# Commodore_CPM_Modul.net
KiCad netlist of a schematic drawn in Altium Designer
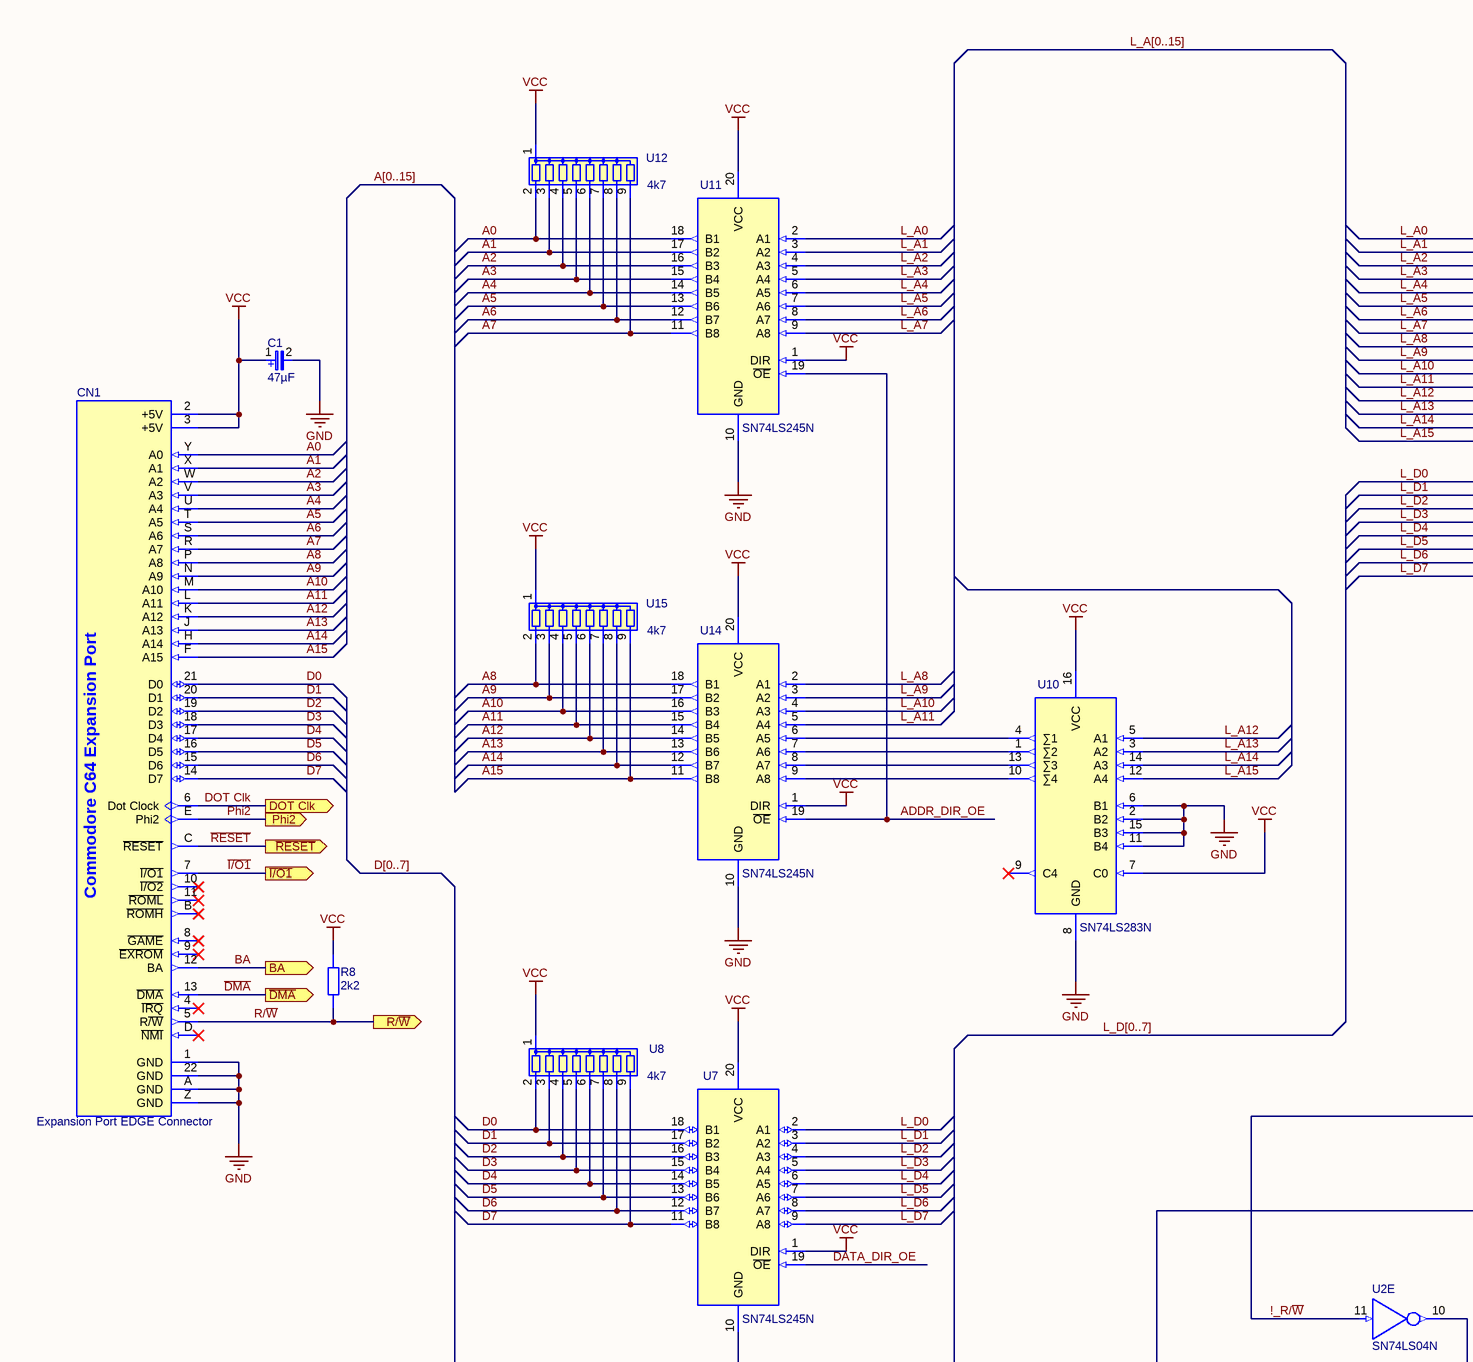
[diagram p0: Commodore CPM Modul.SchDoc, top left]
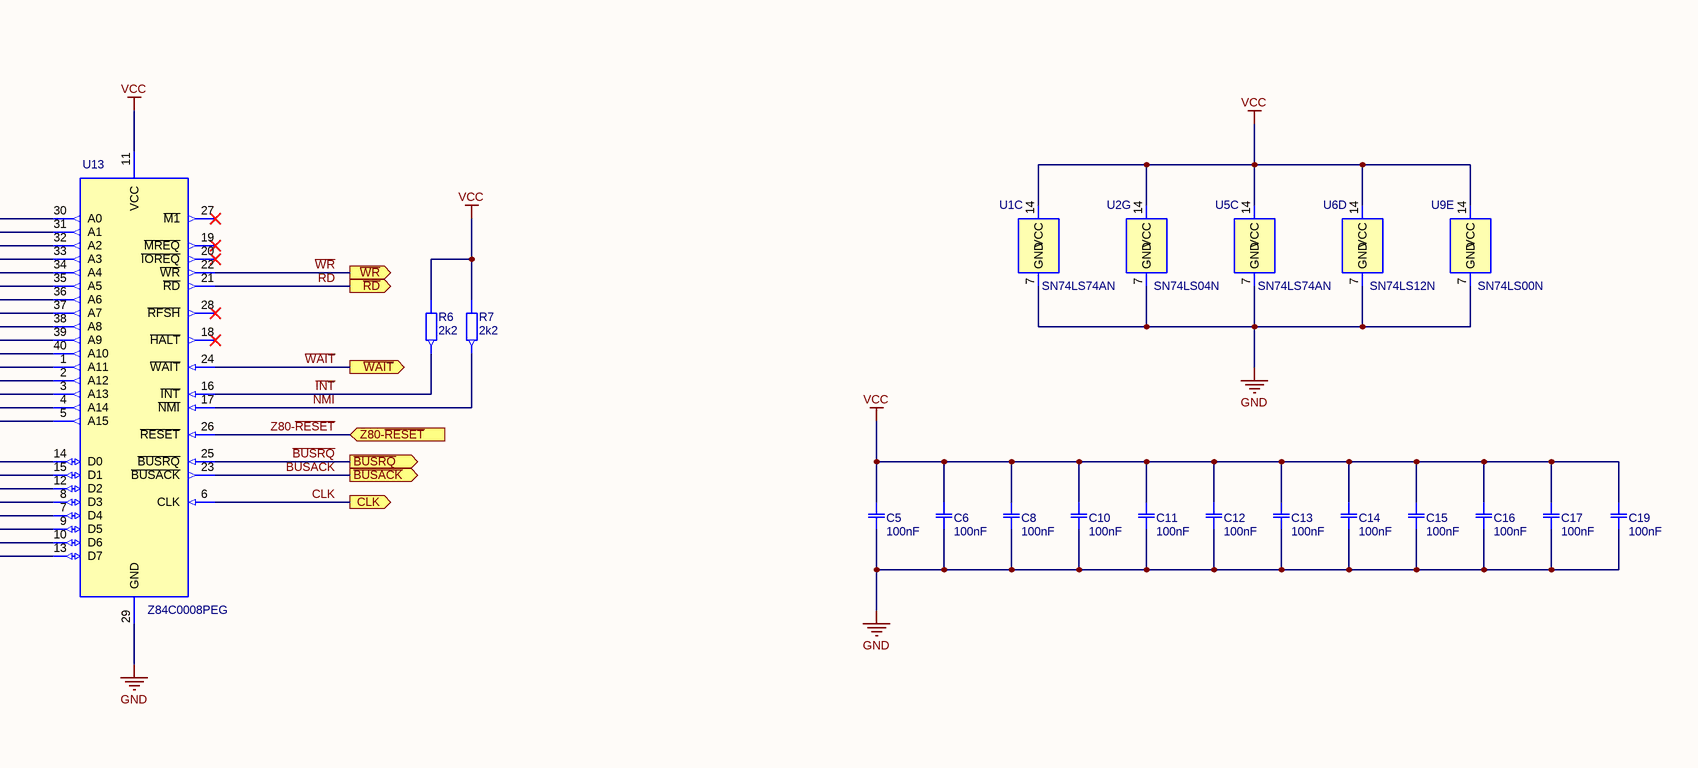
[diagram p1: Commodore CPM Modul.SchDoc, top right]
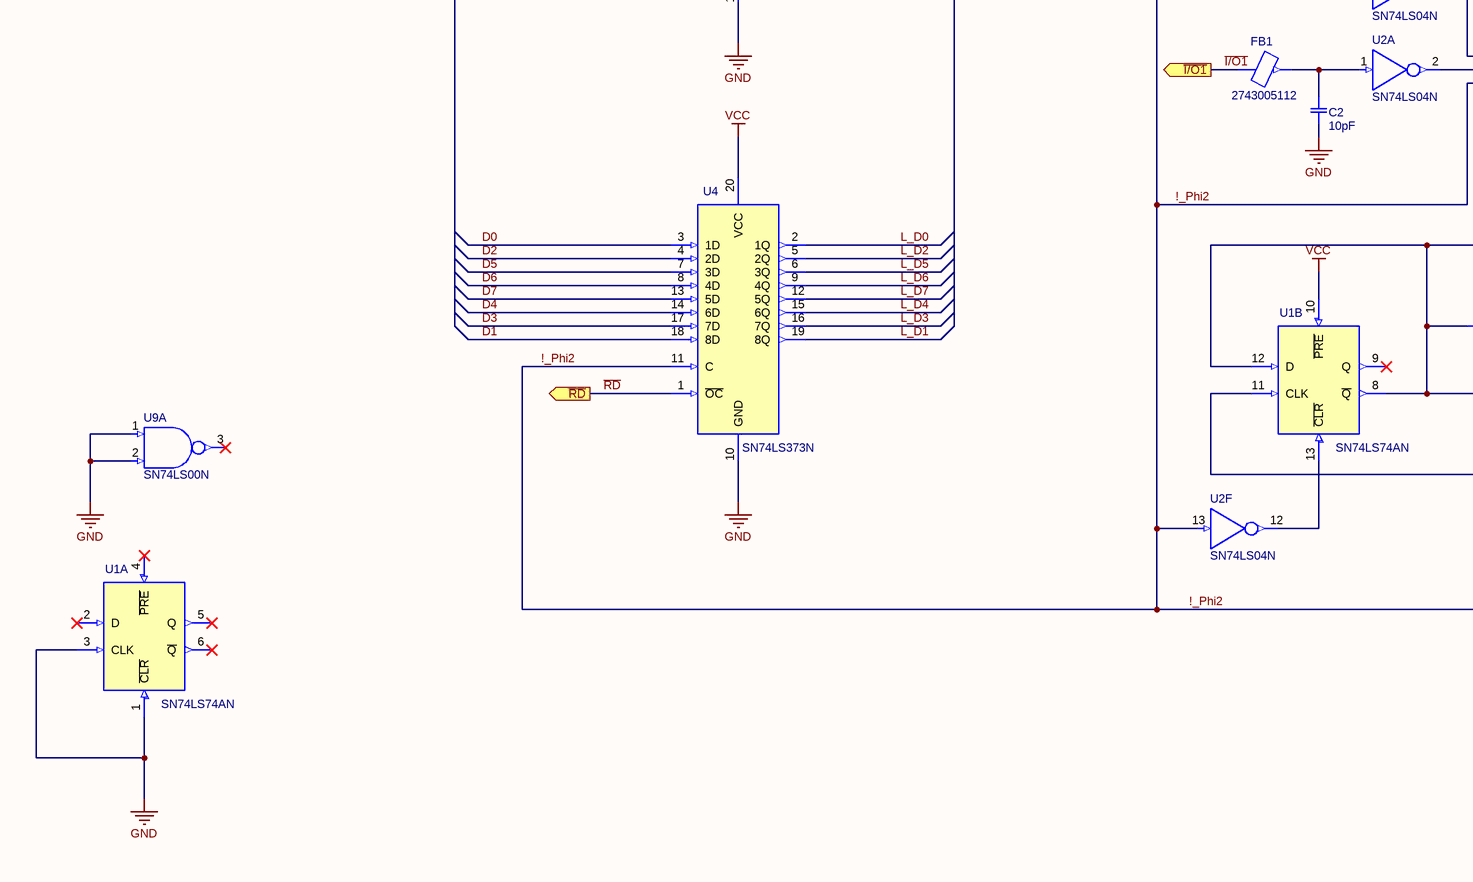
[diagram p2: Commodore CPM Modul.SchDoc, bottom left]
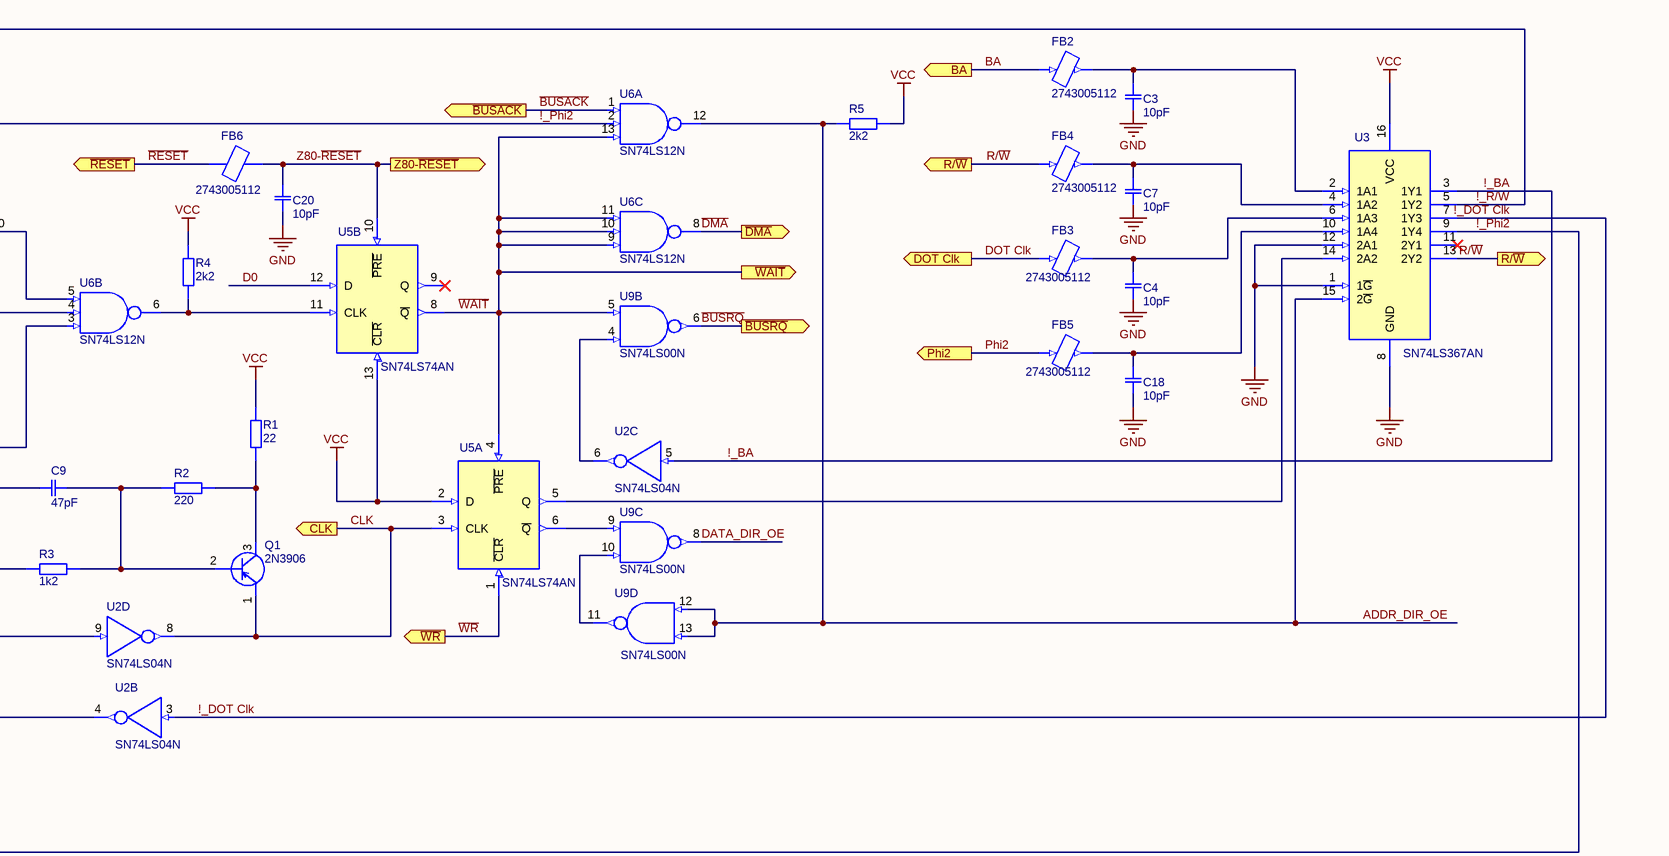
[diagram p3: Commodore CPM Modul.SchDoc, bottom right]

(export (version "E")
  (design (tool "Eeschema 10.0.6"))
  (components
    (comp (ref "C1")
      (value "47µF")
      (footprint "CAP Elec 47uF 25V Axial - Vishay MAL203036479E3")
      (description "Cap Aluminum 47uF 25V -10% to 50% (6 X 10mm) Axial 4.8 Ohm 100mA 3000 hr 85C Taped in Box")
      (fields (field (name "VOLTAGE") "25V") (field (name "TOLERANCE") "50%"))
      (libsource (lib "PCB-Tech Cloud") (part "Polarized Capacitor"))
    )
    (comp (ref "C2")
      (value "10pF")
      (footprint "CAP CER 10PF 50V C0G/NP0 AXIAL Vishay A100J15C0GF5TAA")
      (description "Cap Ceramic 10pF 50V C0G 5% Axial 125C T/R")
      (fields (field (name "TOLERANCE") "5%"))
      (libsource (lib "PCB-Tech Cloud") (part "Capacitor"))
    )
    (comp (ref "C3")
      (value "10pF")
      (footprint "CAP CER 10PF 50V C0G/NP0 AXIAL Vishay A100J15C0GF5TAA")
      (description "Cap Ceramic 10pF 50V C0G 5% Axial 125C T/R")
      (fields (field (name "TOLERANCE") "5%"))
      (libsource (lib "PCB-Tech Cloud") (part "Capacitor"))
    )
    (comp (ref "C4")
      (value "10pF")
      (footprint "CAP CER 10PF 50V C0G/NP0 AXIAL Vishay A100J15C0GF5TAA")
      (description "Cap Ceramic 10pF 50V C0G 5% Axial 125C T/R")
      (fields (field (name "TOLERANCE") "5%"))
      (libsource (lib "PCB-Tech Cloud") (part "Capacitor"))
    )
    (comp (ref "C5")
      (value "100nF")
      (footprint "CAP CER 0.1UF 50V X7R RADIAL Kemet C330C104J5R5TA")
      (description "Cap Ceramic 0.1uF 50V X7R 5% Radial 5.08mm 125C Bulk")
      (fields (field (name "TOLERANCE") "5%"))
      (libsource (lib "PCB-Tech Cloud") (part "Capacitor"))
    )
    (comp (ref "C6")
      (value "100nF")
      (footprint "CAP CER 0.1UF 50V X7R RADIAL Kemet C330C104J5R5TA")
      (description "Cap Ceramic 0.1uF 50V X7R 5% Radial 5.08mm 125C Bulk")
      (fields (field (name "TOLERANCE") "5%"))
      (libsource (lib "PCB-Tech Cloud") (part "Capacitor"))
    )
    (comp (ref "C7")
      (value "10pF")
      (footprint "CAP CER 10PF 50V C0G/NP0 AXIAL Vishay A100J15C0GF5TAA")
      (description "Cap Ceramic 10pF 50V C0G 5% Axial 125C T/R")
      (fields (field (name "TOLERANCE") "5%"))
      (libsource (lib "PCB-Tech Cloud") (part "Capacitor"))
    )
    (comp (ref "C8")
      (value "100nF")
      (footprint "CAP CER 0.1UF 50V X7R RADIAL Kemet C330C104J5R5TA")
      (description "Cap Ceramic 0.1uF 50V X7R 5% Radial 5.08mm 125C Bulk")
      (fields (field (name "TOLERANCE") "5%"))
      (libsource (lib "PCB-Tech Cloud") (part "Capacitor"))
    )
    (comp (ref "C9")
      (value "47pF")
      (footprint "CAP CER 47PF 50V C0G/NP0 AXIAL Vishay A470J15C0GF5TAA")
      (description "Cap Ceramic 47pF 50V C0G 5% Axial 125C T/R")
      (fields (field (name "TOLERANCE") "5%"))
      (libsource (lib "PCB-Tech Cloud") (part "Capacitor"))
    )
    (comp (ref "C10")
      (value "100nF")
      (footprint "CAP CER 0.1UF 50V X7R RADIAL Kemet C330C104J5R5TA")
      (description "Cap Ceramic 0.1uF 50V X7R 5% Radial 5.08mm 125C Bulk")
      (fields (field (name "TOLERANCE") "5%"))
      (libsource (lib "PCB-Tech Cloud") (part "Capacitor"))
    )
    (comp (ref "C11")
      (value "100nF")
      (footprint "CAP CER 0.1UF 50V X7R RADIAL Kemet C330C104J5R5TA")
      (description "Cap Ceramic 0.1uF 50V X7R 5% Radial 5.08mm 125C Bulk")
      (fields (field (name "TOLERANCE") "5%"))
      (libsource (lib "PCB-Tech Cloud") (part "Capacitor"))
    )
    (comp (ref "C12")
      (value "100nF")
      (footprint "CAP CER 0.1UF 50V X7R RADIAL Kemet C330C104J5R5TA")
      (description "Cap Ceramic 0.1uF 50V X7R 5% Radial 5.08mm 125C Bulk")
      (fields (field (name "TOLERANCE") "5%"))
      (libsource (lib "PCB-Tech Cloud") (part "Capacitor"))
    )
    (comp (ref "C13")
      (value "100nF")
      (footprint "CAP CER 0.1UF 50V X7R RADIAL Kemet C330C104J5R5TA")
      (description "Cap Ceramic 0.1uF 50V X7R 5% Radial 5.08mm 125C Bulk")
      (fields (field (name "TOLERANCE") "5%"))
      (libsource (lib "PCB-Tech Cloud") (part "Capacitor"))
    )
    (comp (ref "C14")
      (value "100nF")
      (footprint "CAP CER 0.1UF 50V X7R RADIAL Kemet C330C104J5R5TA")
      (description "Cap Ceramic 0.1uF 50V X7R 5% Radial 5.08mm 125C Bulk")
      (fields (field (name "TOLERANCE") "5%"))
      (libsource (lib "PCB-Tech Cloud") (part "Capacitor"))
    )
    (comp (ref "C15")
      (value "100nF")
      (footprint "CAP CER 0.1UF 50V X7R RADIAL Kemet C330C104J5R5TA")
      (description "Cap Ceramic 0.1uF 50V X7R 5% Radial 5.08mm 125C Bulk")
      (fields (field (name "TOLERANCE") "5%"))
      (libsource (lib "PCB-Tech Cloud") (part "Capacitor"))
    )
    (comp (ref "C16")
      (value "100nF")
      (footprint "CAP CER 0.1UF 50V X7R RADIAL Kemet C330C104J5R5TA")
      (description "Cap Ceramic 0.1uF 50V X7R 5% Radial 5.08mm 125C Bulk")
      (fields (field (name "TOLERANCE") "5%"))
      (libsource (lib "PCB-Tech Cloud") (part "Capacitor"))
    )
    (comp (ref "C17")
      (value "100nF")
      (footprint "CAP CER 0.1UF 50V X7R RADIAL Kemet C330C104J5R5TA")
      (description "Cap Ceramic 0.1uF 50V X7R 5% Radial 5.08mm 125C Bulk")
      (fields (field (name "TOLERANCE") "5%"))
      (libsource (lib "PCB-Tech Cloud") (part "Capacitor"))
    )
    (comp (ref "C18")
      (value "10pF")
      (footprint "CAP CER 10PF 50V C0G/NP0 AXIAL Vishay A100J15C0GF5TAA")
      (description "Cap Ceramic 10pF 50V C0G 5% Axial 125C T/R")
      (fields (field (name "TOLERANCE") "5%"))
      (libsource (lib "PCB-Tech Cloud") (part "Capacitor"))
    )
    (comp (ref "C19")
      (value "100nF")
      (footprint "CAP CER 0.1UF 50V X7R RADIAL Kemet C330C104J5R5TA")
      (description "Cap Ceramic 0.1uF 50V X7R 5% Radial 5.08mm 125C Bulk")
      (fields (field (name "TOLERANCE") "5%"))
      (libsource (lib "PCB-Tech Cloud") (part "Capacitor"))
    )
    (comp (ref "C20")
      (value "10pF")
      (footprint "CAP CER 10PF 50V C0G/NP0 AXIAL Vishay A100J15C0GF5TAA")
      (description "Cap Ceramic 10pF 50V C0G 5% Axial 125C T/R")
      (fields (field (name "TOLERANCE") "5%"))
      (libsource (lib "PCB-Tech Cloud") (part "Capacitor"))
    )
    (comp (ref "CN1")
      (value "Expansion Port EDGE Connector")
      (footprint "C64 Expansion Port EDGE Connector")
      (description "Expansion Port EDGE Connector for Interface Cards")
      (libsource (lib "PCB-Tech Cloud") (part "C64 Expansion Port"))
    )
    (comp (ref "FB1")
      (value "2743005112")
      (footprint "Ferrite Bead Fair Rite 2743005112 axial 10,16mm")
      (description "Ferrite Beads Axial 91Ohm 100MHz T/R")
      (libsource (lib "PCB-Tech Cloud") (part "Ferrite Bead"))
    )
    (comp (ref "FB2")
      (value "2743005112")
      (footprint "Ferrite Bead Fair Rite 2743005112 axial 10,16mm")
      (description "Ferrite Beads Axial 91Ohm 100MHz T/R")
      (libsource (lib "PCB-Tech Cloud") (part "Ferrite Bead"))
    )
    (comp (ref "FB3")
      (value "2743005112")
      (footprint "Ferrite Bead Fair Rite 2743005112 axial 10,16mm")
      (description "Ferrite Beads Axial 91Ohm 100MHz T/R")
      (libsource (lib "PCB-Tech Cloud") (part "Ferrite Bead"))
    )
    (comp (ref "FB4")
      (value "2743005112")
      (footprint "Ferrite Bead Fair Rite 2743005112 axial 10,16mm")
      (description "Ferrite Beads Axial 91Ohm 100MHz T/R")
      (libsource (lib "PCB-Tech Cloud") (part "Ferrite Bead"))
    )
    (comp (ref "FB5")
      (value "2743005112")
      (footprint "Ferrite Bead Fair Rite 2743005112 axial 10,16mm")
      (description "Ferrite Beads Axial 91Ohm 100MHz T/R")
      (libsource (lib "PCB-Tech Cloud") (part "Ferrite Bead"))
    )
    (comp (ref "FB6")
      (value "2743005112")
      (footprint "Ferrite Bead Fair Rite 2743005112 axial 10,16mm")
      (description "Ferrite Beads Axial 91Ohm 100MHz T/R")
      (libsource (lib "PCB-Tech Cloud") (part "Ferrite Bead"))
    )
    (comp (ref "Q1")
      (value "2N3906")
      (footprint "2N3906")
      (description "Bipolar Transistor PNP Amplifier/Switch 40V 200mA 3-Pin TO-92 Through Hole Box")
      (libsource (lib "PCB-Tech Cloud") (part "Transistor PNP EBC"))
    )
    (comp (ref "R1")
      (value "22")
      (footprint "22 Ohm R Axial DIN0207 L6.3mm D2.5mm P10.16mm Horizontal")
      (description "RES 22 OHM 1/4W 5% AXIAL")
      (fields (field (name "TOLERANCE") "5%"))
      (libsource (lib "PCB-Tech Cloud") (part "Resistor"))
    )
    (comp (ref "R2")
      (value "220")
      (footprint "220 Ohm R Axial DIN0207 L6.3mm D2.5mm P10.16mm Horizontal")
      (description "RES 220 OHM 1/4W 5% AXIAL")
      (fields (field (name "TOLERANCE") "5%"))
      (libsource (lib "PCB-Tech Cloud") (part "Resistor"))
    )
    (comp (ref "R3")
      (value "1k2")
      (footprint "1,2 kOhm R Axial DIN0207 L6.3mm D2.5mm P10.16mm Horizontal")
      (description "RES 1.2K OHM 1/4W 5% AXIAL")
      (fields (field (name "TOLERANCE") "5%"))
      (libsource (lib "PCB-Tech Cloud") (part "Resistor"))
    )
    (comp (ref "R4")
      (value "2k2")
      (footprint "2,2 kOhm R Axial DIN0207 L6.3mm D2.5mm P10.16mm Horizontal")
      (description "RES 2.2K OHM 1/4W 5% AXIAL")
      (fields (field (name "TOLERANCE") "5%"))
      (libsource (lib "PCB-Tech Cloud") (part "Resistor"))
    )
    (comp (ref "R5")
      (value "2k2")
      (footprint "2,2 kOhm R Axial DIN0207 L6.3mm D2.5mm P10.16mm Horizontal")
      (description "RES 2.2K OHM 1/4W 5% AXIAL")
      (fields (field (name "TOLERANCE") "5%"))
      (libsource (lib "PCB-Tech Cloud") (part "Resistor"))
    )
    (comp (ref "R6")
      (value "2k2")
      (footprint "2,2 kOhm R Axial DIN0207 L6.3mm D2.5mm P10.16mm Horizontal")
      (description "RES 2.2K OHM 1/4W 5% AXIAL")
      (fields (field (name "TOLERANCE") "5%"))
      (libsource (lib "") (part "Resistor_1"))
    )
    (comp (ref "R7")
      (value "2k2")
      (footprint "2,2 kOhm R Axial DIN0207 L6.3mm D2.5mm P10.16mm Horizontal")
      (description "RES 2.2K OHM 1/4W 5% AXIAL")
      (fields (field (name "TOLERANCE") "5%"))
      (libsource (lib "") (part "Resistor_1"))
    )
    (comp (ref "R8")
      (value "2k2")
      (footprint "2,2 kOhm R Axial DIN0207 L6.3mm D2.5mm P10.16mm Horizontal")
      (description "RES 2.2K OHM 1/4W 5% AXIAL")
      (fields (field (name "TOLERANCE") "5%"))
      (libsource (lib "PCB-Tech Cloud") (part "Resistor"))
    )
    (comp (ref "U1")
      (value "SN74LS74AN")
      (footprint "SN74LS74N with Socket")
      (libsource (lib "PCB-Tech Cloud") (part "74xx74"))
    )
    (comp (ref "U2")
      (value "SN74LS04N")
      (footprint "SN74LS04N with Socket")
      (description "IC HEX INVERTER 14-DIP")
      (libsource (lib "PCB-Tech Cloud") (part "74xx04"))
    )
    (comp (ref "U3")
      (value "SN74LS367AN")
      (footprint "SN74LS367A with Socket")
      (description "I.C. SN74LS 367 AN")
      (libsource (lib "PCB-Tech Cloud") (part "74xx367"))
    )
    (comp (ref "U4")
      (value "SN74LS373N")
      (footprint "SN74LS373N with Socket")
      (description "Latch Transparent 3-ST 8-CH D-Type 20-Pin PDIP Tube")
      (libsource (lib "PCB-Tech Cloud") (part "74xx373"))
    )
    (comp (ref "U5")
      (value "SN74LS74AN")
      (footprint "SN74LS74N with Socket")
      (libsource (lib "PCB-Tech Cloud") (part "74xx74"))
    )
    (comp (ref "U6")
      (value "SN74LS12N")
      (footprint "SN74LS12N with Socket")
      (description "Logic Gates Triple 3-input Positive-NAND gates with open collector outputs 14-PDIP 0 to 70")
      (libsource (lib "") (part "74xx12_1"))
    )
    (comp (ref "U7")
      (value "SN74LS245N")
      (footprint "SN74LS245N with Socket")
      (description "IC TXRX NON-INVERT 5.25V 20DIP")
      (libsource (lib "PCB-Tech Cloud") (part "74xx245"))
    )
    (comp (ref "U8")
      (value "4k7")
      (footprint "4k7 x8 Resistor Array SIL Royal 9A472G")
      (description "Resistor Networks & Arrays 9pin 4.7Kohms 2% Bussed")
      (fields (field (name "TOLERANCE") "2%"))
      (libsource (lib "PCB-Tech Cloud") (part "Resistor Network x8"))
    )
    (comp (ref "U9")
      (value "SN74LS00N")
      (footprint "SN74LS00N with Socket")
      (description "IC, 74LS, 74LS00, DIP14, 5.25V")
      (libsource (lib "") (part "74xx00_2"))
    )
    (comp (ref "U10")
      (value "SN74LS283N")
      (footprint "SN74LS283N with Socket")
      (description "Binary Full Adder Single 4-Bit 16-Pin PDIP Box")
      (libsource (lib "PCB-Tech Cloud") (part "74xx283"))
    )
    (comp (ref "U11")
      (value "SN74LS245N")
      (footprint "SN74LS245N with Socket")
      (description "IC TXRX NON-INVERT 5.25V 20DIP")
      (libsource (lib "PCB-Tech Cloud") (part "74xx245"))
    )
    (comp (ref "U12")
      (value "4k7")
      (footprint "4k7 x8 Resistor Array SIL Royal 9A472G")
      (description "Resistor Networks & Arrays 9pin 4.7Kohms 2% Bussed")
      (fields (field (name "TOLERANCE") "2%"))
      (libsource (lib "PCB-Tech Cloud") (part "Resistor Network x8"))
    )
    (comp (ref "U13")
      (value "Z84C0008PEG")
      (footprint "Zilog Z80 CPU with Socket")
      (description "IC MPU Z80 8MHZ 40DIP")
      (fields (field (name "VOLTAGE") "5V"))
      (libsource (lib "PCB-Tech Cloud") (part "Zilog Z80 CPU"))
    )
    (comp (ref "U14")
      (value "SN74LS245N")
      (footprint "SN74LS245N with Socket")
      (description "IC TXRX NON-INVERT 5.25V 20DIP")
      (libsource (lib "PCB-Tech Cloud") (part "74xx245"))
    )
    (comp (ref "U15")
      (value "4k7")
      (footprint "4k7 x8 Resistor Array SIL Royal 9A472G")
      (description "Resistor Networks & Arrays 9pin 4.7Kohms 2% Bussed")
      (fields (field (name "TOLERANCE") "2%"))
      (libsource (lib "PCB-Tech Cloud") (part "Resistor Network x8"))
    )
  )
  (nets
    (net (code "1") (name "/!_BA") (class "Default")
      (node (ref "U2") (pin "5") (pinfunction "3A_5") (pintype "input"))
      (node (ref "U3") (pin "3") (pinfunction "1Y1_3") (pintype "open_collector"))
    )
    (net (code "2") (name "/!_DOT Clk") (class "Default")
      (node (ref "U2") (pin "3") (pinfunction "2A_3") (pintype "input"))
      (node (ref "U3") (pin "7") (pinfunction "1Y3_7") (pintype "open_collector"))
    )
    (net (code "3") (name "/!_Phi2") (class "Default")
      (node (ref "U2") (pin "13") (pinfunction "6A_13") (pintype "input"))
      (node (ref "U3") (pin "9") (pinfunction "1Y4_9") (pintype "open_collector"))
      (node (ref "U4") (pin "11") (pinfunction "C_11") (pintype "input"))
      (node (ref "U6") (pin "2") (pinfunction "1B_2") (pintype "input"))
      (node (ref "U6") (pin "3") (pinfunction "2A_3") (pintype "input"))
    )
    (net (code "4") (name "/!_R{slash}~{W}") (class "Default")
      (node (ref "U2") (pin "11") (pinfunction "5A_11") (pintype "input"))
      (node (ref "U3") (pin "5") (pinfunction "1Y2_5") (pintype "open_collector"))
    )
    (net (code "5") (name "/A0") (class "Default")
      (node (ref "CN1") (pin "Y") (pinfunction "A0_Y") (pintype "input"))
      (node (ref "U11") (pin "18") (pinfunction "B1_18") (pintype "output"))
      (node (ref "U12") (pin "2") (pinfunction "2_2") (pintype "passive"))
    )
    (net (code "6") (name "/A1") (class "Default")
      (node (ref "CN1") (pin "X") (pinfunction "A1_X") (pintype "input"))
      (node (ref "U11") (pin "17") (pinfunction "B2_17") (pintype "output"))
      (node (ref "U12") (pin "3") (pinfunction "3_3") (pintype "passive"))
    )
    (net (code "7") (name "/A2") (class "Default")
      (node (ref "CN1") (pin "W") (pinfunction "A2_W") (pintype "input"))
      (node (ref "U11") (pin "16") (pinfunction "B3_16") (pintype "output"))
      (node (ref "U12") (pin "4") (pinfunction "4_4") (pintype "passive"))
    )
    (net (code "8") (name "/A3") (class "Default")
      (node (ref "CN1") (pin "V") (pinfunction "A3_V") (pintype "input"))
      (node (ref "U11") (pin "15") (pinfunction "B4_15") (pintype "output"))
      (node (ref "U12") (pin "5") (pinfunction "5_5") (pintype "passive"))
    )
    (net (code "9") (name "/A4") (class "Default")
      (node (ref "CN1") (pin "U") (pinfunction "A4_U") (pintype "input"))
      (node (ref "U11") (pin "14") (pinfunction "B5_14") (pintype "output"))
      (node (ref "U12") (pin "6") (pinfunction "6_6") (pintype "passive"))
    )
    (net (code "10") (name "/A5") (class "Default")
      (node (ref "CN1") (pin "T") (pinfunction "A5_T") (pintype "input"))
      (node (ref "U11") (pin "13") (pinfunction "B6_13") (pintype "output"))
      (node (ref "U12") (pin "7") (pinfunction "7_7") (pintype "passive"))
    )
    (net (code "11") (name "/A6") (class "Default")
      (node (ref "CN1") (pin "S") (pinfunction "A6_S") (pintype "input"))
      (node (ref "U11") (pin "12") (pinfunction "B7_12") (pintype "output"))
      (node (ref "U12") (pin "8") (pinfunction "8_8") (pintype "passive"))
    )
    (net (code "12") (name "/A7") (class "Default")
      (node (ref "CN1") (pin "R") (pinfunction "A7_R") (pintype "input"))
      (node (ref "U11") (pin "11") (pinfunction "B8_11") (pintype "output"))
      (node (ref "U12") (pin "9") (pinfunction "9_9") (pintype "passive"))
    )
    (net (code "13") (name "/A8") (class "Default")
      (node (ref "CN1") (pin "P") (pinfunction "A8_P") (pintype "input"))
      (node (ref "U14") (pin "18") (pinfunction "B1_18") (pintype "output"))
      (node (ref "U15") (pin "2") (pinfunction "2_2") (pintype "passive"))
    )
    (net (code "14") (name "/A9") (class "Default")
      (node (ref "CN1") (pin "N") (pinfunction "A9_N") (pintype "input"))
      (node (ref "U14") (pin "17") (pinfunction "B2_17") (pintype "output"))
      (node (ref "U15") (pin "3") (pinfunction "3_3") (pintype "passive"))
    )
    (net (code "15") (name "/A10") (class "Default")
      (node (ref "CN1") (pin "M") (pinfunction "A10_M") (pintype "input"))
      (node (ref "U14") (pin "16") (pinfunction "B3_16") (pintype "output"))
      (node (ref "U15") (pin "4") (pinfunction "4_4") (pintype "passive"))
    )
    (net (code "16") (name "/A11") (class "Default")
      (node (ref "CN1") (pin "L") (pinfunction "A11_L") (pintype "input"))
      (node (ref "U14") (pin "15") (pinfunction "B4_15") (pintype "output"))
      (node (ref "U15") (pin "5") (pinfunction "5_5") (pintype "passive"))
    )
    (net (code "17") (name "/A12") (class "Default")
      (node (ref "CN1") (pin "K") (pinfunction "A12_K") (pintype "input"))
      (node (ref "U14") (pin "14") (pinfunction "B5_14") (pintype "output"))
      (node (ref "U15") (pin "6") (pinfunction "6_6") (pintype "passive"))
    )
    (net (code "18") (name "/A13") (class "Default")
      (node (ref "CN1") (pin "J") (pinfunction "A13_J") (pintype "input"))
      (node (ref "U14") (pin "13") (pinfunction "B6_13") (pintype "output"))
      (node (ref "U15") (pin "7") (pinfunction "7_7") (pintype "passive"))
    )
    (net (code "19") (name "/A14") (class "Default")
      (node (ref "CN1") (pin "H") (pinfunction "A14_H") (pintype "input"))
      (node (ref "U14") (pin "12") (pinfunction "B7_12") (pintype "output"))
      (node (ref "U15") (pin "8") (pinfunction "8_8") (pintype "passive"))
    )
    (net (code "20") (name "/A15") (class "Default")
      (node (ref "CN1") (pin "F") (pinfunction "A15_F") (pintype "input"))
      (node (ref "U14") (pin "11") (pinfunction "B8_11") (pintype "output"))
      (node (ref "U15") (pin "9") (pinfunction "9_9") (pintype "passive"))
    )
    (net (code "21") (name "/ADDR_DIR_OE") (class "Default")
      (node (ref "R5") (pin "1") (pinfunction "1_1") (pintype "passive"))
      (node (ref "U11") (pin "19") (pinfunction "~{OE}_19") (pintype "input"))
      (node (ref "U14") (pin "19") (pinfunction "~{OE}_19") (pintype "input"))
      (node (ref "U3") (pin "15") (pinfunction "2~{G}_15") (pintype "input"))
      (node (ref "U6") (pin "12") (pinfunction "1Y_12") (pintype "open_collector"))
      (node (ref "U9") (pin "12") (pinfunction "4B_12") (pintype "input"))
      (node (ref "U9") (pin "13") (pinfunction "4A_13") (pintype "input"))
    )
    (net (code "23") (name "/BA") (class "Default")
      (node (ref "CN1") (pin "12") (pinfunction "BA_12") (pintype "output"))
      (node (ref "FB2") (pin "1") (pinfunction "1_1") (pintype "passive"))
    )
    (net (code "24") (name "/CLK") (class "Default")
      (node (ref "Q1") (pin "1") (pinfunction "1_1") (pintype "passive"))
      (node (ref "U13") (pin "6") (pinfunction "CLK_6") (pintype "input"))
      (node (ref "U2") (pin "8") (pinfunction "4Y_8") (pintype "output"))
      (node (ref "U5") (pin "3") (pinfunction "CLK_3") (pintype "input"))
    )
    (net (code "25") (name "/D0") (class "Default")
      (node (ref "CN1") (pin "21") (pinfunction "D0_21") (pintype "bidirectional"))
      (node (ref "U4") (pin "3") (pinfunction "1D_3") (pintype "input"))
      (node (ref "U5") (pin "12") (pinfunction "D_12") (pintype "input"))
      (node (ref "U7") (pin "18") (pinfunction "B1_18") (pintype "output"))
      (node (ref "U8") (pin "2") (pinfunction "2_2") (pintype "passive"))
    )
    (net (code "26") (name "/D1") (class "Default")
      (node (ref "CN1") (pin "20") (pinfunction "D1_20") (pintype "bidirectional"))
      (node (ref "U4") (pin "18") (pinfunction "8D_18") (pintype "input"))
      (node (ref "U7") (pin "17") (pinfunction "B2_17") (pintype "output"))
      (node (ref "U8") (pin "3") (pinfunction "3_3") (pintype "passive"))
    )
    (net (code "27") (name "/D2") (class "Default")
      (node (ref "CN1") (pin "19") (pinfunction "D2_19") (pintype "bidirectional"))
      (node (ref "U4") (pin "4") (pinfunction "2D_4") (pintype "input"))
      (node (ref "U7") (pin "16") (pinfunction "B3_16") (pintype "output"))
      (node (ref "U8") (pin "4") (pinfunction "4_4") (pintype "passive"))
    )
    (net (code "28") (name "/D3") (class "Default")
      (node (ref "CN1") (pin "18") (pinfunction "D3_18") (pintype "bidirectional"))
      (node (ref "U4") (pin "17") (pinfunction "7D_17") (pintype "input"))
      (node (ref "U7") (pin "15") (pinfunction "B4_15") (pintype "output"))
      (node (ref "U8") (pin "5") (pinfunction "5_5") (pintype "passive"))
    )
    (net (code "29") (name "/D4") (class "Default")
      (node (ref "CN1") (pin "17") (pinfunction "D4_17") (pintype "bidirectional"))
      (node (ref "U4") (pin "14") (pinfunction "6D_14") (pintype "input"))
      (node (ref "U7") (pin "14") (pinfunction "B5_14") (pintype "output"))
      (node (ref "U8") (pin "6") (pinfunction "6_6") (pintype "passive"))
    )
    (net (code "30") (name "/D5") (class "Default")
      (node (ref "CN1") (pin "16") (pinfunction "D5_16") (pintype "bidirectional"))
      (node (ref "U4") (pin "7") (pinfunction "3D_7") (pintype "input"))
      (node (ref "U7") (pin "13") (pinfunction "B6_13") (pintype "output"))
      (node (ref "U8") (pin "7") (pinfunction "7_7") (pintype "passive"))
    )
    (net (code "31") (name "/D6") (class "Default")
      (node (ref "CN1") (pin "15") (pinfunction "D6_15") (pintype "bidirectional"))
      (node (ref "U4") (pin "8") (pinfunction "4D_8") (pintype "input"))
      (node (ref "U7") (pin "12") (pinfunction "B7_12") (pintype "output"))
      (node (ref "U8") (pin "8") (pinfunction "8_8") (pintype "passive"))
    )
    (net (code "32") (name "/D7") (class "Default")
      (node (ref "CN1") (pin "14") (pinfunction "D7_14") (pintype "bidirectional"))
      (node (ref "U4") (pin "13") (pinfunction "5D_13") (pintype "input"))
      (node (ref "U7") (pin "11") (pinfunction "B8_11") (pintype "output"))
      (node (ref "U8") (pin "9") (pinfunction "9_9") (pintype "passive"))
    )
    (net (code "33") (name "/DATA_DIR_OE") (class "Default")
      (node (ref "U7") (pin "19") (pinfunction "~{OE}_19") (pintype "input"))
      (node (ref "U9") (pin "8") (pinfunction "3Y_8") (pintype "output"))
    )
    (net (code "34") (name "/DOT Clk") (class "Default")
      (node (ref "CN1") (pin "6") (pinfunction "Dot_Clock_6") (pintype "output"))
      (node (ref "FB3") (pin "1") (pinfunction "1_1") (pintype "passive"))
    )
    (net (code "36") (name "/L_A0") (class "Default")
      (node (ref "U11") (pin "2") (pinfunction "A1_2") (pintype "input"))
      (node (ref "U13") (pin "30") (pinfunction "A0_30") (pintype "output"))
    )
    (net (code "37") (name "/L_A1") (class "Default")
      (node (ref "U11") (pin "3") (pinfunction "A2_3") (pintype "input"))
      (node (ref "U13") (pin "31") (pinfunction "A1_31") (pintype "output"))
    )
    (net (code "38") (name "/L_A2") (class "Default")
      (node (ref "U11") (pin "4") (pinfunction "A3_4") (pintype "input"))
      (node (ref "U13") (pin "32") (pinfunction "A2_32") (pintype "output"))
    )
    (net (code "39") (name "/L_A3") (class "Default")
      (node (ref "U11") (pin "5") (pinfunction "A4_5") (pintype "input"))
      (node (ref "U13") (pin "33") (pinfunction "A3_33") (pintype "output"))
    )
    (net (code "40") (name "/L_A4") (class "Default")
      (node (ref "U11") (pin "6") (pinfunction "A5_6") (pintype "input"))
      (node (ref "U13") (pin "34") (pinfunction "A4_34") (pintype "output"))
    )
    (net (code "41") (name "/L_A5") (class "Default")
      (node (ref "U11") (pin "7") (pinfunction "A6_7") (pintype "input"))
      (node (ref "U13") (pin "35") (pinfunction "A5_35") (pintype "output"))
    )
    (net (code "42") (name "/L_A6") (class "Default")
      (node (ref "U11") (pin "8") (pinfunction "A7_8") (pintype "input"))
      (node (ref "U13") (pin "36") (pinfunction "A6_36") (pintype "output"))
    )
    (net (code "43") (name "/L_A7") (class "Default")
      (node (ref "U11") (pin "9") (pinfunction "A8_9") (pintype "input"))
      (node (ref "U13") (pin "37") (pinfunction "A7_37") (pintype "output"))
    )
    (net (code "44") (name "/L_A8") (class "Default")
      (node (ref "U13") (pin "38") (pinfunction "A8_38") (pintype "output"))
      (node (ref "U14") (pin "2") (pinfunction "A1_2") (pintype "input"))
    )
    (net (code "45") (name "/L_A9") (class "Default")
      (node (ref "U13") (pin "39") (pinfunction "A9_39") (pintype "output"))
      (node (ref "U14") (pin "3") (pinfunction "A2_3") (pintype "input"))
    )
    (net (code "46") (name "/L_A10") (class "Default")
      (node (ref "U13") (pin "40") (pinfunction "A10_40") (pintype "output"))
      (node (ref "U14") (pin "4") (pinfunction "A3_4") (pintype "input"))
    )
    (net (code "47") (name "/L_A11") (class "Default")
      (node (ref "U13") (pin "1") (pinfunction "A11_1") (pintype "output"))
      (node (ref "U14") (pin "5") (pinfunction "A4_5") (pintype "input"))
    )
    (net (code "48") (name "/L_A12") (class "Default")
      (node (ref "U10") (pin "5") (pinfunction "A1_5") (pintype "input"))
      (node (ref "U13") (pin "2") (pinfunction "A12_2") (pintype "output"))
    )
    (net (code "49") (name "/L_A13") (class "Default")
      (node (ref "U10") (pin "3") (pinfunction "A2_3") (pintype "input"))
      (node (ref "U13") (pin "3") (pinfunction "A13_3") (pintype "output"))
    )
    (net (code "50") (name "/L_A14") (class "Default")
      (node (ref "U10") (pin "14") (pinfunction "A3_14") (pintype "input"))
      (node (ref "U13") (pin "4") (pinfunction "A14_4") (pintype "output"))
    )
    (net (code "51") (name "/L_A15") (class "Default")
      (node (ref "U10") (pin "12") (pinfunction "A4_12") (pintype "input"))
      (node (ref "U13") (pin "5") (pinfunction "A15_5") (pintype "output"))
    )
    (net (code "53") (name "/L_D0") (class "Default")
      (node (ref "U13") (pin "14") (pinfunction "D0_14") (pintype "bidirectional"))
      (node (ref "U4") (pin "2") (pinfunction "1Q_2") (pintype "output"))
      (node (ref "U7") (pin "2") (pinfunction "A1_2") (pintype "input"))
    )
    (net (code "54") (name "/L_D1") (class "Default")
      (node (ref "U13") (pin "15") (pinfunction "D1_15") (pintype "bidirectional"))
      (node (ref "U4") (pin "19") (pinfunction "8Q_19") (pintype "output"))
      (node (ref "U7") (pin "3") (pinfunction "A2_3") (pintype "input"))
    )
    (net (code "55") (name "/L_D2") (class "Default")
      (node (ref "U13") (pin "12") (pinfunction "D2_12") (pintype "bidirectional"))
      (node (ref "U4") (pin "5") (pinfunction "2Q_5") (pintype "output"))
      (node (ref "U7") (pin "4") (pinfunction "A3_4") (pintype "input"))
    )
    (net (code "56") (name "/L_D3") (class "Default")
      (node (ref "U13") (pin "8") (pinfunction "D3_8") (pintype "bidirectional"))
      (node (ref "U4") (pin "16") (pinfunction "7Q_16") (pintype "output"))
      (node (ref "U7") (pin "5") (pinfunction "A4_5") (pintype "input"))
    )
    (net (code "57") (name "/L_D4") (class "Default")
      (node (ref "U13") (pin "7") (pinfunction "D4_7") (pintype "bidirectional"))
      (node (ref "U4") (pin "15") (pinfunction "6Q_15") (pintype "output"))
      (node (ref "U7") (pin "6") (pinfunction "A5_6") (pintype "input"))
    )
    (net (code "58") (name "/L_D5") (class "Default")
      (node (ref "U13") (pin "9") (pinfunction "D5_9") (pintype "bidirectional"))
      (node (ref "U4") (pin "6") (pinfunction "3Q_6") (pintype "output"))
      (node (ref "U7") (pin "7") (pinfunction "A6_7") (pintype "input"))
    )
    (net (code "59") (name "/L_D6") (class "Default")
      (node (ref "U13") (pin "10") (pinfunction "D6_10") (pintype "bidirectional"))
      (node (ref "U4") (pin "9") (pinfunction "4Q_9") (pintype "output"))
      (node (ref "U7") (pin "8") (pinfunction "A7_8") (pintype "input"))
    )
    (net (code "60") (name "/L_D7") (class "Default")
      (node (ref "U13") (pin "13") (pinfunction "D7_13") (pintype "bidirectional"))
      (node (ref "U4") (pin "12") (pinfunction "5Q_12") (pintype "output"))
      (node (ref "U7") (pin "9") (pinfunction "A8_9") (pintype "input"))
    )
    (net (code "62") (name "/Phi2") (class "Default")
      (node (ref "CN1") (pin "E") (pinfunction "Phi2_E") (pintype "output"))
      (node (ref "FB5") (pin "1") (pinfunction "1_1") (pintype "passive"))
    )
    (net (code "63") (name "/R{slash}~{W}") (class "Default")
      (node (ref "CN1") (pin "5") (pinfunction "R~{/W}_5") (pintype "output"))
      (node (ref "FB4") (pin "1") (pinfunction "1_1") (pintype "passive"))
      (node (ref "R8") (pin "2") (pinfunction "2_2") (pintype "passive"))
      (node (ref "U3") (pin "13") (pinfunction "2Y2_13") (pintype "passive"))
    )
    (net (code "64") (name "/Z80-~{RESET}") (class "Default")
      (node (ref "C20") (pin "2") (pinfunction "2_2") (pintype "passive"))
      (node (ref "FB6") (pin "2") (pinfunction "2_2") (pintype "output"))
      (node (ref "U13") (pin "26") (pinfunction "~{RESET}_26") (pintype "input"))
      (node (ref "U5") (pin "10") (pinfunction "~{PRE}_10") (pintype "input"))
    )
    (net (code "65") (name "/~{BUSACK}") (class "Default")
      (node (ref "U13") (pin "23") (pinfunction "~{BUSACK}_23") (pintype "output"))
      (node (ref "U6") (pin "1") (pinfunction "1A_1") (pintype "input"))
    )
    (net (code "66") (name "/~{BUSRQ}") (class "Default")
      (node (ref "U13") (pin "25") (pinfunction "~{BUSRQ}_25") (pintype "input"))
      (node (ref "U9") (pin "6") (pinfunction "2Y_6") (pintype "output"))
    )
    (net (code "67") (name "/~{DMA}") (class "Default")
      (node (ref "CN1") (pin "13") (pinfunction "~{DMA}_13") (pintype "input"))
      (node (ref "U6") (pin "8") (pinfunction "3Y_8") (pintype "open_collector"))
    )
    (net (code "68") (name "/~{INT}") (class "Default")
      (node (ref "R6") (pin "2") (pinfunction "2_2") (pintype "output"))
      (node (ref "U13") (pin "16") (pinfunction "~{INT}_16") (pintype "input"))
    )
    (net (code "69") (name "/~{I{slash}O1}") (class "Default")
      (node (ref "CN1") (pin "7") (pinfunction "~{I/O1}_7") (pintype "output"))
      (node (ref "FB1") (pin "1") (pinfunction "1_1") (pintype "passive"))
    )
    (net (code "70") (name "/~{NMI}") (class "Default")
      (node (ref "R7") (pin "2") (pinfunction "2_2") (pintype "output"))
      (node (ref "U13") (pin "17") (pinfunction "~{NMI}_17") (pintype "input"))
    )
    (net (code "71") (name "/~{RD}") (class "Default")
      (node (ref "U13") (pin "21") (pinfunction "~{RD}_21") (pintype "output"))
      (node (ref "U4") (pin "1") (pinfunction "~{OC}_1") (pintype "input"))
    )
    (net (code "72") (name "/~{RESET}") (class "Default")
      (node (ref "CN1") (pin "C") (pinfunction "~{RESET}_C") (pintype "output"))
      (node (ref "FB6") (pin "1") (pinfunction "1_1") (pintype "passive"))
    )
    (net (code "73") (name "/~{WAIT}") (class "Default")
      (node (ref "U13") (pin "24") (pinfunction "~{WAIT}_24") (pintype "input"))
      (node (ref "U5") (pin "4") (pinfunction "~{PRE}_4") (pintype "input"))
      (node (ref "U5") (pin "8") (pinfunction "~{Q}_8") (pintype "output"))
      (node (ref "U6") (pin "10") (pinfunction "3C_10") (pintype "input"))
      (node (ref "U6") (pin "11") (pinfunction "3B_11") (pintype "input"))
      (node (ref "U6") (pin "13") (pinfunction "1C_13") (pintype "input"))
      (node (ref "U6") (pin "9") (pinfunction "3A_9") (pintype "input"))
      (node (ref "U9") (pin "5") (pinfunction "2B_5") (pintype "input"))
    )
    (net (code "74") (name "/~{WR}") (class "Default")
      (node (ref "U13") (pin "22") (pinfunction "~{WR}_22") (pintype "output"))
      (node (ref "U5") (pin "1") (pinfunction "~{CLR}_1") (pintype "input"))
    )
    (net (code "75") (name "GND") (class "Default")
      (node (ref "C1") (pin "2") (pinfunction "2_2") (pintype "passive"))
      (node (ref "C10") (pin "1") (pinfunction "1_1") (pintype "passive"))
      (node (ref "C11") (pin "1") (pinfunction "1_1") (pintype "passive"))
      (node (ref "C12") (pin "1") (pinfunction "1_1") (pintype "passive"))
      (node (ref "C13") (pin "1") (pinfunction "1_1") (pintype "passive"))
      (node (ref "C14") (pin "1") (pinfunction "1_1") (pintype "passive"))
      (node (ref "C15") (pin "1") (pinfunction "1_1") (pintype "passive"))
      (node (ref "C16") (pin "1") (pinfunction "1_1") (pintype "passive"))
      (node (ref "C17") (pin "1") (pinfunction "1_1") (pintype "passive"))
      (node (ref "C18") (pin "1") (pinfunction "1_1") (pintype "passive"))
      (node (ref "C19") (pin "1") (pinfunction "1_1") (pintype "passive"))
      (node (ref "C2") (pin "1") (pinfunction "1_1") (pintype "passive"))
      (node (ref "C20") (pin "1") (pinfunction "1_1") (pintype "passive"))
      (node (ref "C3") (pin "2") (pinfunction "2_2") (pintype "passive"))
      (node (ref "C4") (pin "2") (pinfunction "2_2") (pintype "passive"))
      (node (ref "C5") (pin "1") (pinfunction "1_1") (pintype "passive"))
      (node (ref "C6") (pin "1") (pinfunction "1_1") (pintype "passive"))
      (node (ref "C7") (pin "1") (pinfunction "1_1") (pintype "passive"))
      (node (ref "C8") (pin "1") (pinfunction "1_1") (pintype "passive"))
      (node (ref "CN1") (pin "1") (pinfunction "GND_1") (pintype "power_in"))
      (node (ref "CN1") (pin "22") (pinfunction "GND_22") (pintype "power_in"))
      (node (ref "CN1") (pin "A") (pinfunction "GND_A") (pintype "power_in"))
      (node (ref "CN1") (pin "Z") (pinfunction "GND_Z") (pintype "power_in"))
      (node (ref "U1") (pin "1") (pinfunction "~{CLR}_1") (pintype "input"))
      (node (ref "U1") (pin "3") (pinfunction "CLK_3") (pintype "input"))
      (node (ref "U1") (pin "7") (pinfunction "GND_7") (pintype "passive"))
      (node (ref "U10") (pin "11") (pinfunction "B4_11") (pintype "input"))
      (node (ref "U10") (pin "15") (pinfunction "B3_15") (pintype "input"))
      (node (ref "U10") (pin "2") (pinfunction "B2_2") (pintype "input"))
      (node (ref "U10") (pin "6") (pinfunction "B1_6") (pintype "input"))
      (node (ref "U10") (pin "8") (pinfunction "GND_8") (pintype "power_in"))
      (node (ref "U11") (pin "10") (pinfunction "GND_10") (pintype "passive"))
      (node (ref "U13") (pin "29") (pinfunction "GND_29") (pintype "power_in"))
      (node (ref "U14") (pin "10") (pinfunction "GND_10") (pintype "passive"))
      (node (ref "U2") (pin "7") (pinfunction "GND_7") (pintype "passive"))
      (node (ref "U3") (pin "1") (pinfunction "1~{G}_1") (pintype "input"))
      (node (ref "U3") (pin "12") (pinfunction "2A1_12") (pintype "input"))
      (node (ref "U3") (pin "8") (pinfunction "GND_8") (pintype "power_in"))
      (node (ref "U4") (pin "10") (pinfunction "GND_10") (pintype "power_in"))
      (node (ref "U5") (pin "7") (pinfunction "GND_7") (pintype "passive"))
      (node (ref "U6") (pin "7") (pinfunction "GND_7") (pintype "passive"))
      (node (ref "U7") (pin "10") (pinfunction "GND_10") (pintype "passive"))
      (node (ref "U9") (pin "1") (pinfunction "1A_1") (pintype "input"))
      (node (ref "U9") (pin "2") (pinfunction "1B_2") (pintype "input"))
      (node (ref "U9") (pin "7") (pinfunction "GND_7") (pintype "passive"))
    )
    (net (code "76") (name "Net-(C9-Pad2)") (class "Default")
      (node (ref "C9") (pin "2") (pinfunction "2_2") (pintype "passive"))
      (node (ref "Q1") (pin "2") (pinfunction "2_2") (pintype "passive"))
      (node (ref "R2") (pin "2") (pinfunction "2_2") (pintype "passive"))
      (node (ref "R3") (pin "1") (pinfunction "1_1") (pintype "passive"))
    )
    (net (code "77") (name "Net-(Q1-Pad3)") (class "Default")
      (node (ref "Q1") (pin "3") (pinfunction "3_3") (pintype "passive"))
      (node (ref "R1") (pin "1") (pinfunction "1_1") (pintype "passive"))
      (node (ref "R2") (pin "1") (pinfunction "1_1") (pintype "passive"))
    )
    (net (code "78") (name "Net-(U1B-CLK)") (class "Default")
      (node (ref "U1") (pin "11") (pinfunction "CLK_11") (pintype "input"))
      (node (ref "U2") (pin "4") (pinfunction "2Y_4") (pintype "output"))
    )
    (net (code "79") (name "Net-(U1B-D)") (class "Default")
      (node (ref "C9") (pin "1") (pinfunction "1_1") (pintype "passive"))
      (node (ref "R3") (pin "2") (pinfunction "2_2") (pintype "passive"))
      (node (ref "U1") (pin "12") (pinfunction "D_12") (pintype "input"))
      (node (ref "U1") (pin "8") (pinfunction "~{Q}_8") (pintype "output"))
      (node (ref "U2") (pin "9") (pinfunction "4A_9") (pintype "input"))
    )
    (net (code "80") (name "Net-(U1B-~{CLR})") (class "Default")
      (node (ref "U1") (pin "13") (pinfunction "~{CLR}_13") (pintype "input"))
      (node (ref "U2") (pin "12") (pinfunction "6Y_12") (pintype "output"))
    )
    (net (code "81") (name "Net-(U2A-1A)") (class "Default")
      (node (ref "C2") (pin "2") (pinfunction "2_2") (pintype "passive"))
      (node (ref "FB1") (pin "2") (pinfunction "2_2") (pintype "output"))
      (node (ref "U2") (pin "1") (pinfunction "1A_1") (pintype "input"))
    )
    (net (code "82") (name "Net-(U2A-1Y)") (class "Default")
      (node (ref "U2") (pin "2") (pinfunction "1Y_2") (pintype "output"))
      (node (ref "U6") (pin "4") (pinfunction "2B_4") (pintype "input"))
    )
    (net (code "83") (name "Net-(U2C-3Y)") (class "Default")
      (node (ref "U2") (pin "6") (pinfunction "3Y_6") (pintype "output"))
      (node (ref "U9") (pin "4") (pinfunction "2A_4") (pintype "input"))
    )
    (net (code "84") (name "Net-(U2E-5Y)") (class "Default")
      (node (ref "U2") (pin "10") (pinfunction "5Y_10") (pintype "output"))
      (node (ref "U6") (pin "5") (pinfunction "2C_5") (pintype "input"))
    )
    (net (code "85") (name "Net-(U3-1A1)") (class "Default")
      (node (ref "C3") (pin "1") (pinfunction "1_1") (pintype "passive"))
      (node (ref "FB2") (pin "2") (pinfunction "2_2") (pintype "output"))
      (node (ref "U3") (pin "2") (pinfunction "1A1_2") (pintype "input"))
    )
    (net (code "86") (name "Net-(U3-1A2)") (class "Default")
      (node (ref "C7") (pin "2") (pinfunction "2_2") (pintype "passive"))
      (node (ref "FB4") (pin "2") (pinfunction "2_2") (pintype "output"))
      (node (ref "U3") (pin "4") (pinfunction "1A2_4") (pintype "input"))
    )
    (net (code "87") (name "Net-(U3-1A3)") (class "Default")
      (node (ref "C4") (pin "1") (pinfunction "1_1") (pintype "passive"))
      (node (ref "FB3") (pin "2") (pinfunction "2_2") (pintype "output"))
      (node (ref "U3") (pin "6") (pinfunction "1A3_6") (pintype "input"))
    )
    (net (code "88") (name "Net-(U3-1A4)") (class "Default")
      (node (ref "C18") (pin "2") (pinfunction "2_2") (pintype "passive"))
      (node (ref "FB5") (pin "2") (pinfunction "2_2") (pintype "output"))
      (node (ref "U3") (pin "10") (pinfunction "1A4_10") (pintype "input"))
    )
    (net (code "89") (name "Net-(U3-2A2)") (class "Default")
      (node (ref "U3") (pin "14") (pinfunction "2A2_14") (pintype "input"))
      (node (ref "U5") (pin "5") (pinfunction "Q_5") (pintype "output"))
    )
    (net (code "90") (name "Net-(U5A-~{Q})") (class "Default")
      (node (ref "U5") (pin "6") (pinfunction "~{Q}_6") (pintype "output"))
      (node (ref "U9") (pin "9") (pinfunction "3B_9") (pintype "input"))
    )
    (net (code "91") (name "Net-(U5B-CLK)") (class "Default")
      (node (ref "R4") (pin "1") (pinfunction "1_1") (pintype "passive"))
      (node (ref "U5") (pin "11") (pinfunction "CLK_11") (pintype "input"))
      (node (ref "U6") (pin "6") (pinfunction "2Y_6") (pintype "open_collector"))
    )
    (net (code "92") (name "Net-(U9C-3A)") (class "Default")
      (node (ref "U9") (pin "10") (pinfunction "3A_10") (pintype "input"))
      (node (ref "U9") (pin "11") (pinfunction "4Y_11") (pintype "output"))
    )
    (net (code "93") (name "Net-(U10-∑1)") (class "Default")
      (node (ref "U10") (pin "4") (pinfunction "∑1_4") (pintype "output"))
      (node (ref "U14") (pin "6") (pinfunction "A5_6") (pintype "input"))
    )
    (net (code "94") (name "Net-(U10-∑2)") (class "Default")
      (node (ref "U10") (pin "1") (pinfunction "∑2_1") (pintype "output"))
      (node (ref "U14") (pin "7") (pinfunction "A6_7") (pintype "input"))
    )
    (net (code "95") (name "Net-(U10-∑3)") (class "Default")
      (node (ref "U10") (pin "13") (pinfunction "∑3_13") (pintype "output"))
      (node (ref "U14") (pin "8") (pinfunction "A7_8") (pintype "input"))
    )
    (net (code "96") (name "Net-(U10-∑4)") (class "Default")
      (node (ref "U10") (pin "10") (pinfunction "∑4_10") (pintype "output"))
      (node (ref "U14") (pin "9") (pinfunction "A8_9") (pintype "input"))
    )
    (net (code "97") (name "VCC") (class "Default")
      (node (ref "C1") (pin "1") (pinfunction "1_1") (pintype "passive"))
      (node (ref "C10") (pin "2") (pinfunction "2_2") (pintype "passive"))
      (node (ref "C11") (pin "2") (pinfunction "2_2") (pintype "passive"))
      (node (ref "C12") (pin "2") (pinfunction "2_2") (pintype "passive"))
      (node (ref "C13") (pin "2") (pinfunction "2_2") (pintype "passive"))
      (node (ref "C14") (pin "2") (pinfunction "2_2") (pintype "passive"))
      (node (ref "C15") (pin "2") (pinfunction "2_2") (pintype "passive"))
      (node (ref "C16") (pin "2") (pinfunction "2_2") (pintype "passive"))
      (node (ref "C17") (pin "2") (pinfunction "2_2") (pintype "passive"))
      (node (ref "C19") (pin "2") (pinfunction "2_2") (pintype "passive"))
      (node (ref "C5") (pin "2") (pinfunction "2_2") (pintype "passive"))
      (node (ref "C6") (pin "2") (pinfunction "2_2") (pintype "passive"))
      (node (ref "C8") (pin "2") (pinfunction "2_2") (pintype "passive"))
      (node (ref "CN1") (pin "2") (pinfunction "+5V_2") (pintype "power_in"))
      (node (ref "CN1") (pin "3") (pinfunction "+5V_3") (pintype "power_in"))
      (node (ref "R1") (pin "2") (pinfunction "2_2") (pintype "passive"))
      (node (ref "R4") (pin "2") (pinfunction "2_2") (pintype "passive"))
      (node (ref "R5") (pin "2") (pinfunction "2_2") (pintype "passive"))
      (node (ref "R6") (pin "1") (pinfunction "1_1") (pintype "passive"))
      (node (ref "R7") (pin "1") (pinfunction "1_1") (pintype "passive"))
      (node (ref "R8") (pin "1") (pinfunction "1_1") (pintype "passive"))
      (node (ref "U1") (pin "10") (pinfunction "~{PRE}_10") (pintype "input"))
      (node (ref "U1") (pin "14") (pinfunction "VCC_14") (pintype "power_in"))
      (node (ref "U10") (pin "16") (pinfunction "VCC_16") (pintype "power_in"))
      (node (ref "U10") (pin "7") (pinfunction "C0_7") (pintype "input"))
      (node (ref "U11") (pin "1") (pinfunction "DIR_1") (pintype "input"))
      (node (ref "U11") (pin "20") (pinfunction "VCC_20") (pintype "passive"))
      (node (ref "U12") (pin "1") (pinfunction "1_1") (pintype "passive"))
      (node (ref "U13") (pin "11") (pinfunction "VCC_11") (pintype "power_in"))
      (node (ref "U14") (pin "1") (pinfunction "DIR_1") (pintype "input"))
      (node (ref "U14") (pin "20") (pinfunction "VCC_20") (pintype "passive"))
      (node (ref "U15") (pin "1") (pinfunction "1_1") (pintype "passive"))
      (node (ref "U2") (pin "14") (pinfunction "VCC_14") (pintype "power_in"))
      (node (ref "U3") (pin "16") (pinfunction "VCC_16") (pintype "power_in"))
      (node (ref "U4") (pin "20") (pinfunction "VCC_20") (pintype "power_in"))
      (node (ref "U5") (pin "13") (pinfunction "~{CLR}_13") (pintype "input"))
      (node (ref "U5") (pin "14") (pinfunction "VCC_14") (pintype "power_in"))
      (node (ref "U5") (pin "2") (pinfunction "D_2") (pintype "input"))
      (node (ref "U6") (pin "14") (pinfunction "VCC_14") (pintype "power_in"))
      (node (ref "U7") (pin "1") (pinfunction "DIR_1") (pintype "input"))
      (node (ref "U7") (pin "20") (pinfunction "VCC_20") (pintype "passive"))
      (node (ref "U8") (pin "1") (pinfunction "1_1") (pintype "passive"))
      (node (ref "U9") (pin "14") (pinfunction "VCC_14") (pintype "power_in"))
    )
    (net (code "98") (name "unconnected-(CN1-~{EXROM}-Pad9)") (class "Default")
      (node (ref "CN1") (pin "9") (pinfunction "~{EXROM}_9") (pintype "input+no_connect"))
    )
    (net (code "99") (name "unconnected-(CN1-~{GAME}-Pad8)") (class "Default")
      (node (ref "CN1") (pin "8") (pinfunction "~{GAME}_8") (pintype "input+no_connect"))
    )
    (net (code "100") (name "unconnected-(CN1-~{IRQ}-Pad4)") (class "Default")
      (node (ref "CN1") (pin "4") (pinfunction "~{IRQ}_4") (pintype "input+no_connect"))
    )
    (net (code "101") (name "unconnected-(CN1-~{I{slash}O2}-Pad10)") (class "Default")
      (node (ref "CN1") (pin "10") (pinfunction "~{I/O2}_10") (pintype "output+no_connect"))
    )
    (net (code "102") (name "unconnected-(CN1-~{NMI}-PadD)") (class "Default")
      (node (ref "CN1") (pin "D") (pinfunction "~{NMI}_D") (pintype "input+no_connect"))
    )
    (net (code "103") (name "unconnected-(CN1-~{ROMH}-PadB)") (class "Default")
      (node (ref "CN1") (pin "B") (pinfunction "~{ROMH}_B") (pintype "output+no_connect"))
    )
    (net (code "104") (name "unconnected-(CN1-~{ROML}-Pad11)") (class "Default")
      (node (ref "CN1") (pin "11") (pinfunction "~{ROML}_11") (pintype "output+no_connect"))
    )
    (net (code "105") (name "unconnected-(U1A-D-Pad2)") (class "Default")
      (node (ref "U1") (pin "2") (pinfunction "D_2") (pintype "input+no_connect"))
    )
    (net (code "106") (name "unconnected-(U1A-Q-Pad5)") (class "Default")
      (node (ref "U1") (pin "5") (pinfunction "Q_5") (pintype "output+no_connect"))
    )
    (net (code "107") (name "unconnected-(U1A-~{PRE}-Pad4)") (class "Default")
      (node (ref "U1") (pin "4") (pinfunction "~{PRE}_4") (pintype "input+no_connect"))
    )
    (net (code "108") (name "unconnected-(U1A-~{Q}-Pad6)") (class "Default")
      (node (ref "U1") (pin "6") (pinfunction "~{Q}_6") (pintype "output+no_connect"))
    )
    (net (code "109") (name "unconnected-(U1B-Q-Pad9)") (class "Default")
      (node (ref "U1") (pin "9") (pinfunction "Q_9") (pintype "output+no_connect"))
    )
    (net (code "110") (name "unconnected-(U3-2Y1-Pad11)") (class "Default")
      (node (ref "U3") (pin "11") (pinfunction "2Y1_11") (pintype "open_collector+no_connect"))
    )
    (net (code "111") (name "unconnected-(U5B-Q-Pad9)") (class "Default")
      (node (ref "U5") (pin "9") (pinfunction "Q_9") (pintype "output+no_connect"))
    )
    (net (code "112") (name "unconnected-(U9A-1Y-Pad3)") (class "Default")
      (node (ref "U9") (pin "3") (pinfunction "1Y_3") (pintype "output+no_connect"))
    )
    (net (code "113") (name "unconnected-(U10-C4-Pad9)") (class "Default")
      (node (ref "U10") (pin "9") (pinfunction "C4_9") (pintype "output+no_connect"))
    )
    (net (code "114") (name "unconnected-(U13-~{HALT}-Pad18)") (class "Default")
      (node (ref "U13") (pin "18") (pinfunction "~{HALT}_18") (pintype "output+no_connect"))
    )
    (net (code "115") (name "unconnected-(U13-~{IOREQ}-Pad20)") (class "Default")
      (node (ref "U13") (pin "20") (pinfunction "~{IOREQ}_20") (pintype "output+no_connect"))
    )
    (net (code "116") (name "unconnected-(U13-~{M1}-Pad27)") (class "Default")
      (node (ref "U13") (pin "27") (pinfunction "~{M1}_27") (pintype "output+no_connect"))
    )
    (net (code "117") (name "unconnected-(U13-~{MREQ}-Pad19)") (class "Default")
      (node (ref "U13") (pin "19") (pinfunction "~{MREQ}_19") (pintype "output+no_connect"))
    )
    (net (code "118") (name "unconnected-(U13-~{RFSH}-Pad28)") (class "Default")
      (node (ref "U13") (pin "28") (pinfunction "~{RFSH}_28") (pintype "output+no_connect"))
    )
  )
)
